# PL.net
KiCad netlist of a schematic drawn in EAGLE
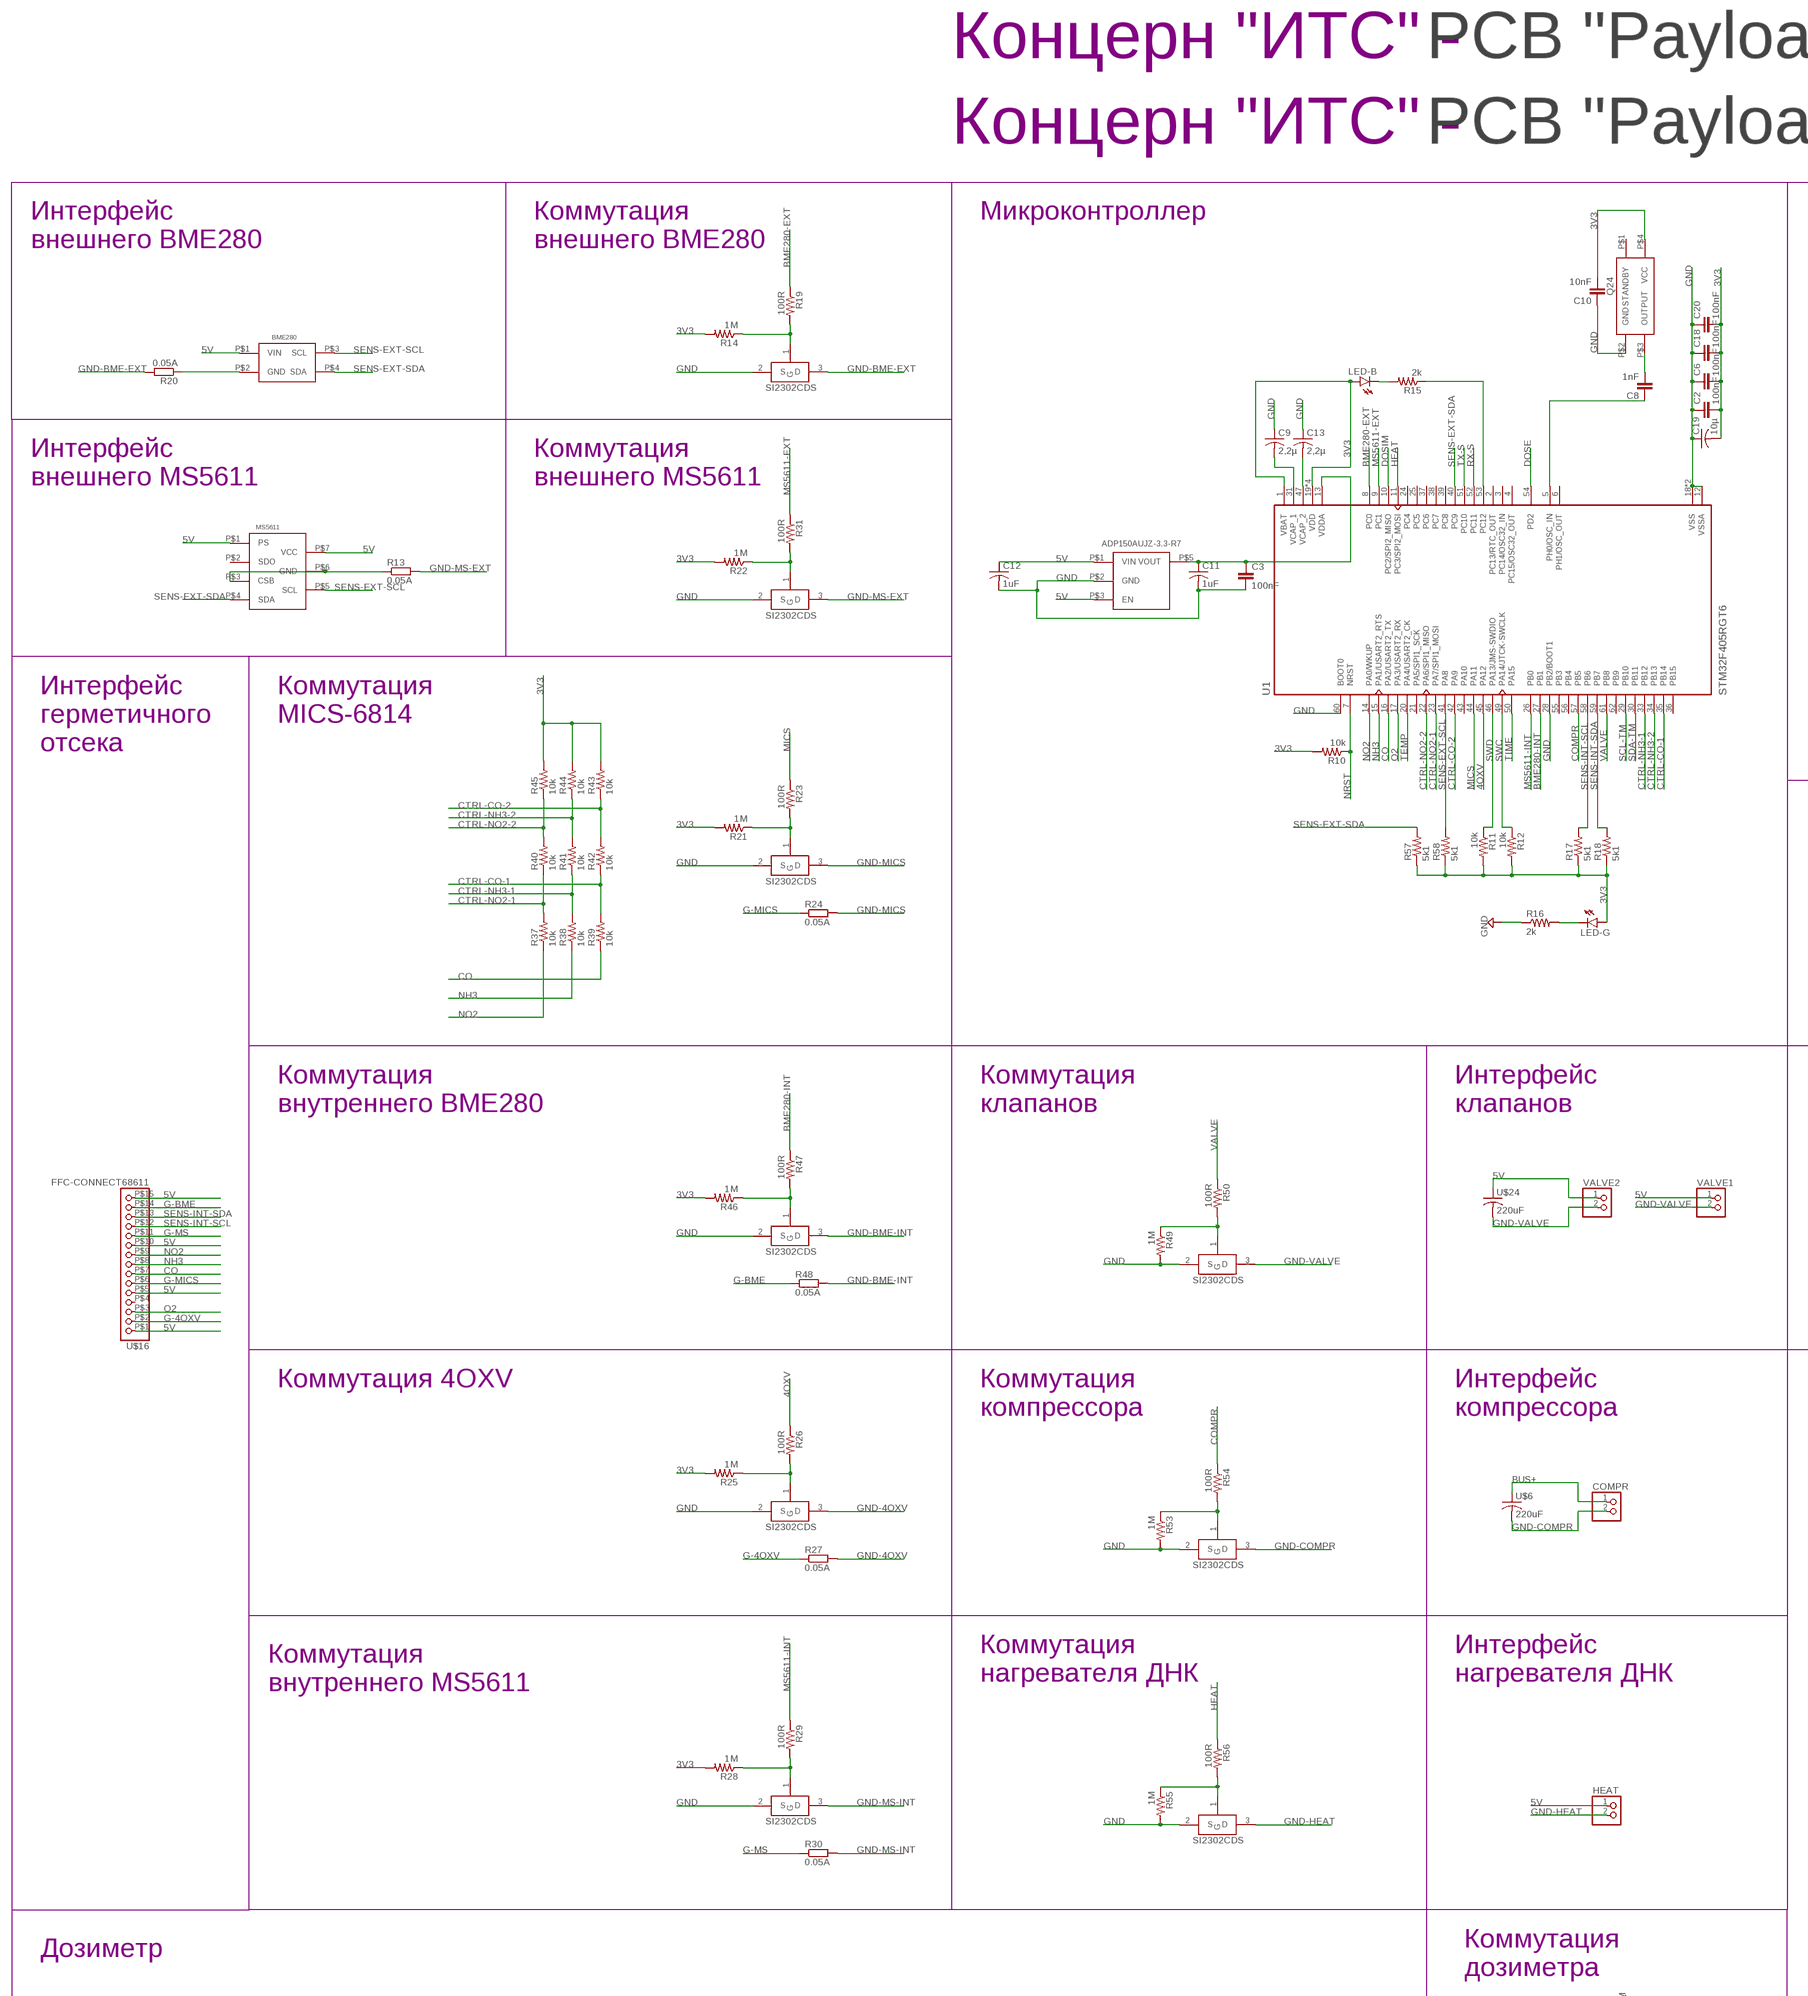
[diagram p0: schematic, sheet 1, part 1 of 3]
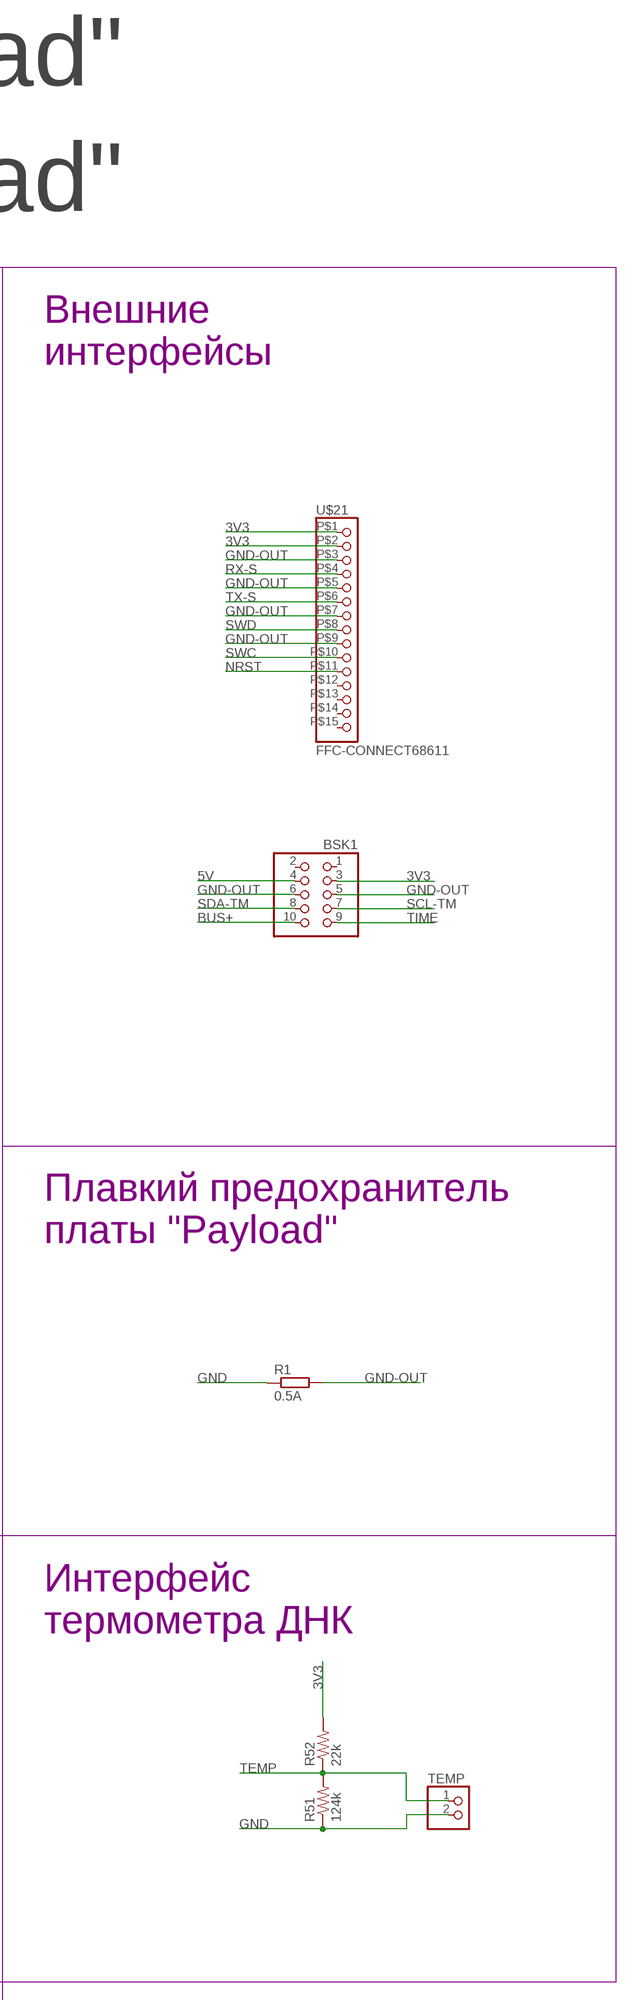
[diagram p1: schematic, sheet 1, part 2 of 3]
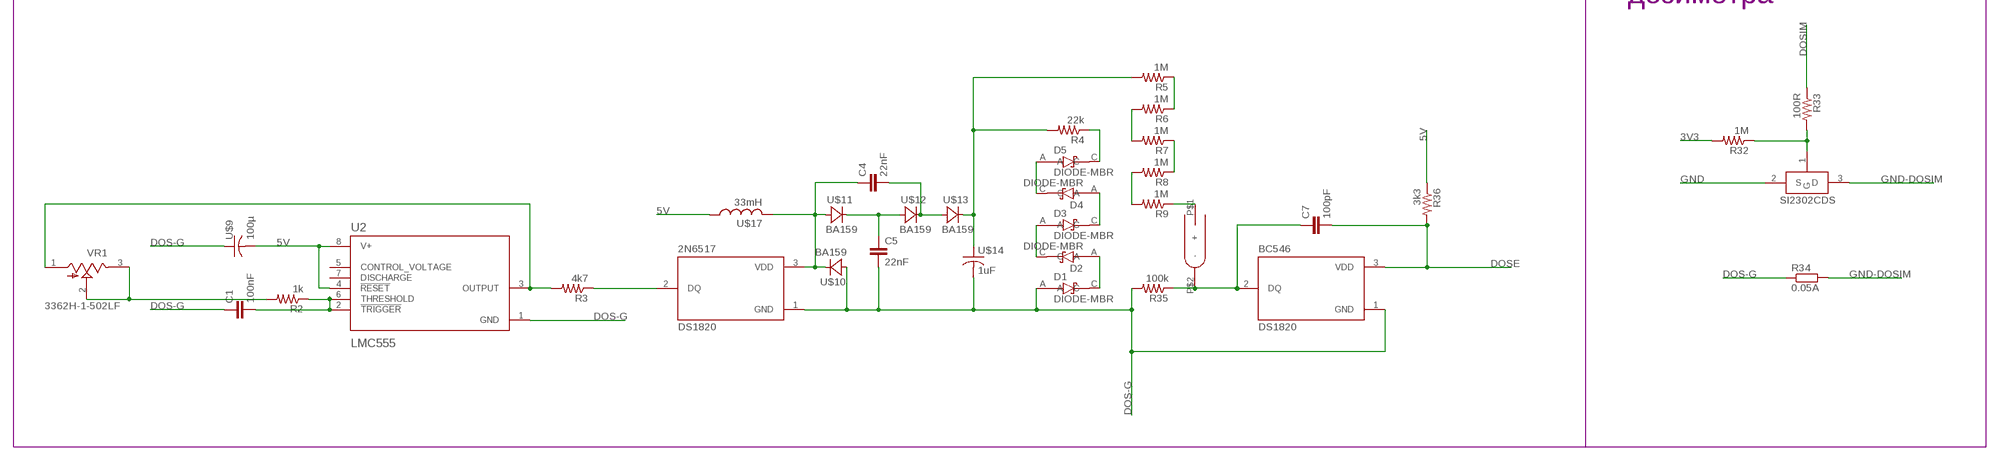
[diagram p2: schematic, sheet 1, part 3 of 3]

(export (version "E")
  (design (tool "Eeschema 10.0.6"))
  (components
    (comp (ref "2N6517")
      (value "DS1820")
      (footprint "eagle-import:TO92_TO226")
      (fields (field (name "MF") "Maxim Integrated"))
      (libsource (lib "eagle-import") (part "DS1820"))
    )
    (comp (ref "BC546")
      (value "DS1820")
      (footprint "eagle-import:TO92_TO226")
      (fields (field (name "MF") "Maxim Integrated"))
      (libsource (lib "eagle-import") (part "DS1820"))
    )
    (comp (ref "BME280")
      (value "BME280BME280-PINS-ONLY")
      (footprint "eagle-import:BME280-PINS-ONLY")
      (libsource (lib "eagle-import") (part "BME280BME280-PINS-ONLY"))
    )
    (comp (ref "BSK1")
      (value "PINHD-2X5")
      (footprint "eagle-import:2X05")
      (libsource (lib "eagle-import") (part "PINHD-2X5"))
    )
    (comp (ref "C1")
      (value "100nF")
      (footprint "eagle-import:C0603")
      (libsource (lib "eagle-import") (part "C-EUC0603"))
    )
    (comp (ref "C2")
      (value "100nF")
      (footprint "eagle-import:C0603")
      (libsource (lib "eagle-import") (part "C-EUC0603"))
    )
    (comp (ref "C3")
      (value "100nF")
      (footprint "eagle-import:C0603")
      (libsource (lib "eagle-import") (part "C-EUC0603"))
    )
    (comp (ref "C4")
      (value "22nF")
      (footprint "eagle-import:C1210")
      (libsource (lib "eagle-import") (part "C-EUC1210"))
    )
    (comp (ref "C5")
      (value "22nF")
      (footprint "eagle-import:C1210")
      (libsource (lib "eagle-import") (part "C-EUC1210"))
    )
    (comp (ref "C6")
      (value "100nF")
      (footprint "eagle-import:C0603")
      (libsource (lib "eagle-import") (part "C-EUC0603"))
    )
    (comp (ref "C7")
      (value "100pF")
      (footprint "eagle-import:C0603")
      (libsource (lib "eagle-import") (part "C-EUC0603"))
    )
    (comp (ref "C8")
      (value "1nF")
      (footprint "eagle-import:C0603")
      (libsource (lib "eagle-import") (part "C-EUC0603"))
    )
    (comp (ref "C9")
      (value "2,2µ")
      (footprint "eagle-import:C0603")
      (libsource (lib "eagle-import") (part "C-USC0603"))
    )
    (comp (ref "C10")
      (value "10nF")
      (footprint "eagle-import:C0603")
      (libsource (lib "eagle-import") (part "C-EUC0603"))
    )
    (comp (ref "C11")
      (value "1uF")
      (footprint "eagle-import:ECAP-SMD-D4")
      (libsource (lib "eagle-import") (part "ECAP1UF"))
    )
    (comp (ref "C12")
      (value "1uF")
      (footprint "eagle-import:ECAP-SMD-D4")
      (libsource (lib "eagle-import") (part "ECAP1UF"))
    )
    (comp (ref "C13")
      (value "2,2µ")
      (footprint "eagle-import:C0603")
      (libsource (lib "eagle-import") (part "C-USC0603"))
    )
    (comp (ref "C18")
      (value "100nF")
      (footprint "eagle-import:C0603")
      (libsource (lib "eagle-import") (part "C-EUC0603"))
    )
    (comp (ref "C19")
      (value "10µ")
      (footprint "eagle-import:C1206")
      (libsource (lib "eagle-import") (part "C-USC1206"))
    )
    (comp (ref "C20")
      (value "100nF")
      (footprint "eagle-import:C0603")
      (libsource (lib "eagle-import") (part "C-EUC0603"))
    )
    (comp (ref "COMPR")
      (value "PINHD-1X2")
      (footprint "eagle-import:1X02")
      (libsource (lib "eagle-import") (part "PINHD-1X2"))
    )
    (comp (ref "D1")
      (value "DIODE-MBR")
      (footprint "eagle-import:SOD123")
      (fields (field (name "MF") "ON Semiconductor") (field (name "MP") "MBR0520LT1G"))
      (libsource (lib "eagle-import") (part "DIODE-MBR"))
    )
    (comp (ref "D2")
      (value "DIODE-MBR")
      (footprint "eagle-import:SOD123")
      (fields (field (name "MF") "ON Semiconductor") (field (name "MP") "MBR0520LT1G"))
      (libsource (lib "eagle-import") (part "DIODE-MBR"))
    )
    (comp (ref "D3")
      (value "DIODE-MBR")
      (footprint "eagle-import:SOD123")
      (fields (field (name "MF") "ON Semiconductor") (field (name "MP") "MBR0520LT1G"))
      (libsource (lib "eagle-import") (part "DIODE-MBR"))
    )
    (comp (ref "D4")
      (value "DIODE-MBR")
      (footprint "eagle-import:SOD123")
      (fields (field (name "MF") "ON Semiconductor") (field (name "MP") "MBR0520LT1G"))
      (libsource (lib "eagle-import") (part "DIODE-MBR"))
    )
    (comp (ref "D5")
      (value "DIODE-MBR")
      (footprint "eagle-import:SOD123")
      (fields (field (name "MF") "ON Semiconductor") (field (name "MP") "MBR0520LT1G"))
      (libsource (lib "eagle-import") (part "DIODE-MBR"))
    )
    (comp (ref "HEAT")
      (value "PINHD-1X2")
      (footprint "eagle-import:1X02")
      (libsource (lib "eagle-import") (part "PINHD-1X2"))
    )
    (comp (ref "LED-B")
      (value "LEDCHIPLED_0603")
      (footprint "eagle-import:CHIPLED_0603")
      (libsource (lib "eagle-import") (part "LEDCHIPLED_0603"))
    )
    (comp (ref "LED-G")
      (value "LEDCHIPLED_0603")
      (footprint "eagle-import:CHIPLED_0603")
      (libsource (lib "eagle-import") (part "LEDCHIPLED_0603"))
    )
    (comp (ref "MS5611")
      (value "MS5611MS5611-PIN-ONLY")
      (footprint "eagle-import:MS5611-PINS-ONLY")
      (libsource (lib "eagle-import") (part "MS5611MS5611-PIN-ONLY"))
    )
    (comp (ref "Q24")
      (value "Q24")
      (footprint "eagle-import:Q24")
      (libsource (lib "eagle-import") (part "Q24"))
    )
    (comp (ref "R1")
      (value "0.5A")
      (footprint "eagle-import:R1210")
      (libsource (lib "eagle-import") (part "R-EU_R1210"))
    )
    (comp (ref "R2")
      (value "1k")
      (footprint "eagle-import:R0603")
      (libsource (lib "eagle-import") (part "R-US_R0603"))
    )
    (comp (ref "R3")
      (value "4k7")
      (footprint "eagle-import:R0603")
      (libsource (lib "eagle-import") (part "R-US_R0603"))
    )
    (comp (ref "R4")
      (value "22k")
      (footprint "eagle-import:R0603")
      (libsource (lib "eagle-import") (part "R-US_R0603"))
    )
    (comp (ref "R5")
      (value "1M")
      (footprint "eagle-import:R0603")
      (libsource (lib "eagle-import") (part "R-US_R0603"))
    )
    (comp (ref "R6")
      (value "1M")
      (footprint "eagle-import:R0603")
      (libsource (lib "eagle-import") (part "R-US_R0603"))
    )
    (comp (ref "R7")
      (value "1M")
      (footprint "eagle-import:R0603")
      (libsource (lib "eagle-import") (part "R-US_R0603"))
    )
    (comp (ref "R8")
      (value "1M")
      (footprint "eagle-import:R0603")
      (libsource (lib "eagle-import") (part "R-US_R0603"))
    )
    (comp (ref "R9")
      (value "1M")
      (footprint "eagle-import:R0603")
      (libsource (lib "eagle-import") (part "R-US_R0603"))
    )
    (comp (ref "R10")
      (value "10k")
      (footprint "eagle-import:R0603")
      (libsource (lib "eagle-import") (part "R-US_R0603"))
    )
    (comp (ref "R11")
      (value "10k")
      (footprint "eagle-import:R0603")
      (libsource (lib "eagle-import") (part "R-US_R0603"))
    )
    (comp (ref "R12")
      (value "10k")
      (footprint "eagle-import:R0603")
      (libsource (lib "eagle-import") (part "R-US_R0603"))
    )
    (comp (ref "R13")
      (value "0.05A")
      (footprint "eagle-import:R1210")
      (libsource (lib "eagle-import") (part "R-EU_R1210"))
    )
    (comp (ref "R14")
      (value "1M")
      (footprint "eagle-import:R0603")
      (libsource (lib "eagle-import") (part "R-US_R0603"))
    )
    (comp (ref "R15")
      (value "2k")
      (footprint "eagle-import:R0603")
      (libsource (lib "eagle-import") (part "R-US_R0603"))
    )
    (comp (ref "R16")
      (value "2k")
      (footprint "eagle-import:R0603")
      (libsource (lib "eagle-import") (part "R-US_R0603"))
    )
    (comp (ref "R17")
      (value "5k1")
      (footprint "eagle-import:R0603")
      (libsource (lib "eagle-import") (part "R-US_R0603"))
    )
    (comp (ref "R18")
      (value "5k1")
      (footprint "eagle-import:R0603")
      (libsource (lib "eagle-import") (part "R-US_R0603"))
    )
    (comp (ref "R19")
      (value "100R")
      (footprint "eagle-import:R0603")
      (libsource (lib "eagle-import") (part "R-US_R0603"))
    )
    (comp (ref "R20")
      (value "0.05A")
      (footprint "eagle-import:R1210")
      (libsource (lib "eagle-import") (part "R-EU_R1210"))
    )
    (comp (ref "R21")
      (value "1M")
      (footprint "eagle-import:R0603")
      (libsource (lib "eagle-import") (part "R-US_R0603"))
    )
    (comp (ref "R22")
      (value "1M")
      (footprint "eagle-import:R0603")
      (libsource (lib "eagle-import") (part "R-US_R0603"))
    )
    (comp (ref "R23")
      (value "100R")
      (footprint "eagle-import:R0603")
      (libsource (lib "eagle-import") (part "R-US_R0603"))
    )
    (comp (ref "R24")
      (value "0.05A")
      (footprint "eagle-import:R1210")
      (libsource (lib "eagle-import") (part "R-EU_R1210"))
    )
    (comp (ref "R25")
      (value "1M")
      (footprint "eagle-import:R0603")
      (libsource (lib "eagle-import") (part "R-US_R0603"))
    )
    (comp (ref "R26")
      (value "100R")
      (footprint "eagle-import:R0603")
      (libsource (lib "eagle-import") (part "R-US_R0603"))
    )
    (comp (ref "R27")
      (value "0.05A")
      (footprint "eagle-import:R1210")
      (libsource (lib "eagle-import") (part "R-EU_R1210"))
    )
    (comp (ref "R28")
      (value "1M")
      (footprint "eagle-import:R0603")
      (libsource (lib "eagle-import") (part "R-US_R0603"))
    )
    (comp (ref "R29")
      (value "100R")
      (footprint "eagle-import:R0603")
      (libsource (lib "eagle-import") (part "R-US_R0603"))
    )
    (comp (ref "R30")
      (value "0.05A")
      (footprint "eagle-import:R1210")
      (libsource (lib "eagle-import") (part "R-EU_R1210"))
    )
    (comp (ref "R31")
      (value "100R")
      (footprint "eagle-import:R0603")
      (libsource (lib "eagle-import") (part "R-US_R0603"))
    )
    (comp (ref "R32")
      (value "1M")
      (footprint "eagle-import:R0603")
      (libsource (lib "eagle-import") (part "R-US_R0603"))
    )
    (comp (ref "R33")
      (value "100R")
      (footprint "eagle-import:R0603")
      (libsource (lib "eagle-import") (part "R-US_R0603"))
    )
    (comp (ref "R34")
      (value "0.05A")
      (footprint "eagle-import:R1210")
      (libsource (lib "eagle-import") (part "R-EU_R1210"))
    )
    (comp (ref "R35")
      (value "100k")
      (footprint "eagle-import:R0603")
      (libsource (lib "eagle-import") (part "R-US_R0603"))
    )
    (comp (ref "R36")
      (value "3k3")
      (footprint "eagle-import:R0603")
      (libsource (lib "eagle-import") (part "R-US_R0603"))
    )
    (comp (ref "R37")
      (value "10k")
      (footprint "eagle-import:R0603")
      (libsource (lib "eagle-import") (part "resistor_348_R-US_R0603"))
    )
    (comp (ref "R38")
      (value "10k")
      (footprint "eagle-import:R0603")
      (libsource (lib "eagle-import") (part "resistor_348_R-US_R0603"))
    )
    (comp (ref "R39")
      (value "10k")
      (footprint "eagle-import:R0603")
      (libsource (lib "eagle-import") (part "resistor_348_R-US_R0603"))
    )
    (comp (ref "R40")
      (value "10k")
      (footprint "eagle-import:R0603")
      (libsource (lib "eagle-import") (part "resistor_348_R-US_R0603"))
    )
    (comp (ref "R41")
      (value "10k")
      (footprint "eagle-import:R0603")
      (libsource (lib "eagle-import") (part "resistor_348_R-US_R0603"))
    )
    (comp (ref "R42")
      (value "10k")
      (footprint "eagle-import:R0603")
      (libsource (lib "eagle-import") (part "resistor_348_R-US_R0603"))
    )
    (comp (ref "R43")
      (value "10k")
      (footprint "eagle-import:R0603")
      (libsource (lib "eagle-import") (part "resistor_348_R-US_R0603"))
    )
    (comp (ref "R44")
      (value "10k")
      (footprint "eagle-import:R0603")
      (libsource (lib "eagle-import") (part "resistor_348_R-US_R0603"))
    )
    (comp (ref "R45")
      (value "10k")
      (footprint "eagle-import:R0603")
      (libsource (lib "eagle-import") (part "resistor_348_R-US_R0603"))
    )
    (comp (ref "R46")
      (value "1M")
      (footprint "eagle-import:R0603")
      (libsource (lib "eagle-import") (part "R-US_R0603"))
    )
    (comp (ref "R47")
      (value "100R")
      (footprint "eagle-import:R0603")
      (libsource (lib "eagle-import") (part "R-US_R0603"))
    )
    (comp (ref "R48")
      (value "0.05A")
      (footprint "eagle-import:R1210")
      (libsource (lib "eagle-import") (part "R-EU_R1210"))
    )
    (comp (ref "R49")
      (value "1M")
      (footprint "eagle-import:R0603")
      (libsource (lib "eagle-import") (part "R-US_R0603"))
    )
    (comp (ref "R50")
      (value "100R")
      (footprint "eagle-import:R0603")
      (libsource (lib "eagle-import") (part "R-US_R0603"))
    )
    (comp (ref "R51")
      (value "124k")
      (footprint "eagle-import:R0603")
      (libsource (lib "eagle-import") (part "resistor_348_R-US_R0603"))
    )
    (comp (ref "R52")
      (value "22k")
      (footprint "eagle-import:R0603")
      (libsource (lib "eagle-import") (part "resistor_348_R-US_R0603"))
    )
    (comp (ref "R53")
      (value "1M")
      (footprint "eagle-import:R0603")
      (libsource (lib "eagle-import") (part "R-US_R0603"))
    )
    (comp (ref "R54")
      (value "100R")
      (footprint "eagle-import:R0603")
      (libsource (lib "eagle-import") (part "R-US_R0603"))
    )
    (comp (ref "R55")
      (value "1M")
      (footprint "eagle-import:R0603")
      (libsource (lib "eagle-import") (part "R-US_R0603"))
    )
    (comp (ref "R56")
      (value "100R")
      (footprint "eagle-import:R0603")
      (libsource (lib "eagle-import") (part "R-US_R0603"))
    )
    (comp (ref "R57")
      (value "5k1")
      (footprint "eagle-import:R0603")
      (libsource (lib "eagle-import") (part "R-US_R0603"))
    )
    (comp (ref "R58")
      (value "5k1")
      (footprint "eagle-import:R0603")
      (libsource (lib "eagle-import") (part "R-US_R0603"))
    )
    (comp (ref "SI2302-0")
      (value "SI2302CDS")
      (footprint "eagle-import:SOT23-3")
      (libsource (lib "eagle-import") (part "SI2302CDS"))
    )
    (comp (ref "SI2302-1")
      (value "SI2302CDS")
      (footprint "eagle-import:SOT23-3")
      (libsource (lib "eagle-import") (part "SI2302CDS"))
    )
    (comp (ref "SI2302-2")
      (value "SI2302CDS")
      (footprint "eagle-import:SOT23-3")
      (libsource (lib "eagle-import") (part "SI2302CDS"))
    )
    (comp (ref "SI2302-3")
      (value "SI2302CDS")
      (footprint "eagle-import:SOT23-3")
      (libsource (lib "eagle-import") (part "SI2302CDS"))
    )
    (comp (ref "SI2302-4")
      (value "SI2302CDS")
      (footprint "eagle-import:SOT23-3")
      (libsource (lib "eagle-import") (part "SI2302CDS"))
    )
    (comp (ref "SI2302-5")
      (value "SI2302CDS")
      (footprint "eagle-import:SOT23-3")
      (libsource (lib "eagle-import") (part "SI2302CDS"))
    )
    (comp (ref "SI2302-6")
      (value "SI2302CDS")
      (footprint "eagle-import:SOT23-3")
      (libsource (lib "eagle-import") (part "SI2302CDS"))
    )
    (comp (ref "SI2302-7")
      (value "SI2302CDS")
      (footprint "eagle-import:SOT23-3")
      (libsource (lib "eagle-import") (part "SI2302CDS"))
    )
    (comp (ref "SI2302-8")
      (value "SI2302CDS")
      (footprint "eagle-import:SOT23-3")
      (libsource (lib "eagle-import") (part "SI2302CDS"))
    )
    (comp (ref "SI2302-9")
      (value "SI2302CDS")
      (footprint "eagle-import:SOT23-3")
      (libsource (lib "eagle-import") (part "SI2302CDS"))
    )
    (comp (ref "STAB")
      (value "ADP150AUJZ-3.3-R7")
      (footprint "eagle-import:SOT23-5")
      (libsource (lib "eagle-import") (part "ADP150AUJZ-3.3-R7"))
    )
    (comp (ref "TEMP")
      (value "PINHD-1X2")
      (footprint "eagle-import:1X02")
      (libsource (lib "eagle-import") (part "PINHD-1X2"))
    )
    (comp (ref "U$1")
      (value "PCB \"Payload\"")
      (footprint "eagle-import:ITS-LOGO")
      (libsource (lib "eagle-import") (part "ITS-LOGOPCB-{dblquote}{dblquote}"))
    )
    (comp (ref "U$6")
      (value "220uF")
      (footprint "eagle-import:ECAP220-CMD")
      (libsource (lib "eagle-import") (part "ECAPECAP220"))
    )
    (comp (ref "U$9")
      (value "100µ")
      (footprint "eagle-import:ECAP100-CMD")
      (libsource (lib "eagle-import") (part "ECAPECAP100"))
    )
    (comp (ref "U$10")
      (value "BA159")
      (footprint "eagle-import:BA159")
      (libsource (lib "eagle-import") (part "BA159"))
    )
    (comp (ref "U$11")
      (value "BA159")
      (footprint "eagle-import:BA159")
      (libsource (lib "eagle-import") (part "BA159"))
    )
    (comp (ref "U$12")
      (value "BA159")
      (footprint "eagle-import:BA159")
      (libsource (lib "eagle-import") (part "BA159"))
    )
    (comp (ref "U$13")
      (value "BA159")
      (footprint "eagle-import:BA159")
      (libsource (lib "eagle-import") (part "BA159"))
    )
    (comp (ref "U$14")
      (value "1uF")
      (footprint "eagle-import:ECAP1MK")
      (libsource (lib "eagle-import") (part "ECAP"))
    )
    (comp (ref "U$15")
      (value "DOSIM")
      (footprint "eagle-import:DOSIM")
      (libsource (lib "eagle-import") (part "DOSIM"))
    )
    (comp (ref "U$16")
      (value "FFC-CONNECT68611")
      (footprint "eagle-import:68611")
      (libsource (lib "eagle-import") (part "FFC-CONNECT68611"))
    )
    (comp (ref "U$17")
      (value "33mH")
      (footprint "eagle-import:RCH114NP")
      (libsource (lib "eagle-import") (part "RCH114NPRCH114NP"))
    )
    (comp (ref "U$21")
      (value "FFC-CONNECT68611")
      (footprint "eagle-import:68611")
      (libsource (lib "eagle-import") (part "FFC-CONNECT68611"))
    )
    (comp (ref "U$24")
      (value "220uF")
      (footprint "eagle-import:ECAP220-CMD")
      (libsource (lib "eagle-import") (part "ECAPECAP220"))
    )
    (comp (ref "U$26")
      (value "PCB \"Payload\"")
      (footprint "eagle-import:ITS-LOGO")
      (libsource (lib "eagle-import") (part "ITS-LOGOPCB-{dblquote}{dblquote}"))
    )
    (comp (ref "U1")
      (value "STM32F405RGT6")
      (footprint "eagle-import:QFP50P1200X1200X160-64N")
      (fields (field (name "DIGI-KEY_PART_NUMBER") "497-11767-ND") (field (name "MF") "STMicroelectronics"))
      (libsource (lib "eagle-import") (part "STM32F405RGT6"))
    )
    (comp (ref "U2")
      (value "LMC555")
      (footprint "eagle-import:SOIC127P599X175-8N")
      (fields (field (name "MF") "Texas Instruments") (field (name "MP") "LMC555CMX/NOPB"))
      (libsource (lib "eagle-import") (part "LMC555CMX/NOPB"))
    )
    (comp (ref "VALVE1")
      (value "PINHD-1X2")
      (footprint "eagle-import:1X02")
      (libsource (lib "eagle-import") (part "PINHD-1X2"))
    )
    (comp (ref "VALVE2")
      (value "PINHD-1X2")
      (footprint "eagle-import:1X02")
      (libsource (lib "eagle-import") (part "PINHD-1X2"))
    )
    (comp (ref "VR1")
      (value "3362H-1-502LF")
      (footprint "eagle-import:TRIM_3362H-1-502LF")
      (fields (field (name "MF") "Bourns") (field (name "MP") "3362P-1-502LF"))
      (libsource (lib "eagle-import") (part "3362H-1-502LF"))
    )
  )
  (nets
    (net (code "1") (name "/3V3") (class "Default")
      (node (ref "BSK1") (pin "3") (pinfunction "3_3") (pintype "passive"))
      (node (ref "C10") (pin "2") (pinfunction "2_2") (pintype "passive"))
      (node (ref "C18") (pin "2") (pinfunction "2_2") (pintype "passive"))
      (node (ref "C19") (pin "2") (pinfunction "2_2") (pintype "passive"))
      (node (ref "C2") (pin "2") (pinfunction "2_2") (pintype "passive"))
      (node (ref "C20") (pin "2") (pinfunction "2_2") (pintype "passive"))
      (node (ref "C6") (pin "2") (pinfunction "2_2") (pintype "passive"))
      (node (ref "LED-B") (pin "A") (pinfunction "A_A") (pintype "passive"))
      (node (ref "LED-G") (pin "A") (pinfunction "A_A") (pintype "passive"))
      (node (ref "Q24") (pin "P$4") (pinfunction "VCC_P$4") (pintype "bidirectional"))
      (node (ref "R10") (pin "2") (pinfunction "2_2") (pintype "passive"))
      (node (ref "R11") (pin "2") (pinfunction "2_2") (pintype "passive"))
      (node (ref "R12") (pin "2") (pinfunction "2_2") (pintype "passive"))
      (node (ref "R14") (pin "2") (pinfunction "2_2") (pintype "passive"))
      (node (ref "R17") (pin "1") (pinfunction "1_1") (pintype "passive"))
      (node (ref "R18") (pin "1") (pinfunction "1_1") (pintype "passive"))
      (node (ref "R21") (pin "2") (pinfunction "2_2") (pintype "passive"))
      (node (ref "R22") (pin "2") (pinfunction "2_2") (pintype "passive"))
      (node (ref "R25") (pin "2") (pinfunction "2_2") (pintype "passive"))
      (node (ref "R28") (pin "2") (pinfunction "2_2") (pintype "passive"))
      (node (ref "R32") (pin "2") (pinfunction "2_2") (pintype "passive"))
      (node (ref "R43") (pin "2") (pinfunction "2_2") (pintype "passive"))
      (node (ref "R44") (pin "2") (pinfunction "2_2") (pintype "passive"))
      (node (ref "R45") (pin "2") (pinfunction "2_2") (pintype "passive"))
      (node (ref "R46") (pin "2") (pinfunction "2_2") (pintype "passive"))
      (node (ref "R52") (pin "2") (pinfunction "2_2") (pintype "passive"))
      (node (ref "R57") (pin "1") (pinfunction "1_1") (pintype "passive"))
      (node (ref "R58") (pin "1") (pinfunction "1_1") (pintype "passive"))
      (node (ref "U$21") (pin "P$1") (pinfunction "1_P$1") (pintype "passive"))
      (node (ref "U$21") (pin "P$2") (pinfunction "2_P$2") (pintype "passive"))
      (node (ref "U1") (pin "1") (pinfunction "VBAT_1") (pintype "power_in"))
      (node (ref "U1") (pin "19") (pinfunction "VDD_19") (pintype "power_in"))
      (node (ref "U1") (pin "32") (pinfunction "VDD_32") (pintype "power_in"))
      (node (ref "U1") (pin "48") (pinfunction "VDD_48") (pintype "power_in"))
      (node (ref "U1") (pin "64") (pinfunction "VDD_64") (pintype "power_in"))
    )
    (net (code "2") (name "/4OXV") (class "Default")
      (node (ref "R26") (pin "1") (pinfunction "1_1") (pintype "passive"))
      (node (ref "U1") (pin "45") (pinfunction "PA12_45") (pintype "bidirectional"))
    )
    (net (code "3") (name "/5V") (class "Default")
      (node (ref "BME280") (pin "P$1") (pinfunction "VIN_P$1") (pintype "bidirectional"))
      (node (ref "BSK1") (pin "4") (pinfunction "4_4") (pintype "passive"))
      (node (ref "C12") (pin "P+") (pinfunction "1_P+") (pintype "passive"))
      (node (ref "HEAT") (pin "1") (pinfunction "1_1") (pintype "passive"))
      (node (ref "MS5611") (pin "P$1") (pinfunction "PS_P$1") (pintype "bidirectional"))
      (node (ref "MS5611") (pin "P$7") (pinfunction "VCC_P$7") (pintype "bidirectional"))
      (node (ref "R36") (pin "1") (pinfunction "1_1") (pintype "passive"))
      (node (ref "STAB") (pin "P$1") (pinfunction "VIN_P$1") (pintype "bidirectional"))
      (node (ref "STAB") (pin "P$3") (pinfunction "EN_P$3") (pintype "bidirectional"))
      (node (ref "U$16") (pin "P$1") (pinfunction "1_P$1") (pintype "passive"))
      (node (ref "U$16") (pin "P$10") (pinfunction "10_P$10") (pintype "passive"))
      (node (ref "U$16") (pin "P$15") (pinfunction "15_P$15") (pintype "passive"))
      (node (ref "U$16") (pin "P$5") (pinfunction "5_P$5") (pintype "passive"))
      (node (ref "U$17") (pin "P$1") (pinfunction "1_P$1") (pintype "passive"))
      (node (ref "U$24") (pin "P$1") (pinfunction "1_P$1") (pintype "passive"))
      (node (ref "U$9") (pin "P$2") (pinfunction "2_P$2") (pintype "passive"))
      (node (ref "U2") (pin "4") (pinfunction "~{RESET}_4") (pintype "input"))
      (node (ref "U2") (pin "8") (pinfunction "V+_8") (pintype "power_in"))
      (node (ref "VALVE1") (pin "1") (pinfunction "1_1") (pintype "passive"))
      (node (ref "VALVE2") (pin "1") (pinfunction "1_1") (pintype "passive"))
    )
    (net (code "4") (name "/BME280-EXT") (class "Default")
      (node (ref "R19") (pin "1") (pinfunction "1_1") (pintype "passive"))
      (node (ref "U1") (pin "8") (pinfunction "PC0_8") (pintype "bidirectional"))
    )
    (net (code "5") (name "/BME280-INT") (class "Default")
      (node (ref "R47") (pin "1") (pinfunction "1_1") (pintype "passive"))
      (node (ref "U1") (pin "27") (pinfunction "PB1_27") (pintype "bidirectional"))
    )
    (net (code "6") (name "/BUS+") (class "Default")
      (node (ref "BSK1") (pin "10") (pinfunction "10_10") (pintype "passive"))
      (node (ref "COMPR") (pin "1") (pinfunction "1_1") (pintype "passive"))
      (node (ref "U$6") (pin "P$1") (pinfunction "1_P$1") (pintype "passive"))
    )
    (net (code "7") (name "/CO") (class "Default")
      (node (ref "R39") (pin "1") (pinfunction "1_1") (pintype "passive"))
      (node (ref "U$16") (pin "P$7") (pinfunction "7_P$7") (pintype "passive"))
      (node (ref "U1") (pin "16") (pinfunction "PA2/USART2_TX_16") (pintype "bidirectional"))
    )
    (net (code "8") (name "/COMPR") (class "Default")
      (node (ref "R54") (pin "1") (pinfunction "1_1") (pintype "passive"))
      (node (ref "U1") (pin "57") (pinfunction "PB5_57") (pintype "bidirectional"))
    )
    (net (code "9") (name "/CTRL-CO-1") (class "Default")
      (node (ref "R39") (pin "2") (pinfunction "2_2") (pintype "passive"))
      (node (ref "R42") (pin "1") (pinfunction "1_1") (pintype "passive"))
      (node (ref "U1") (pin "35") (pinfunction "PB14_35") (pintype "bidirectional"))
    )
    (net (code "10") (name "/CTRL-CO-2") (class "Default")
      (node (ref "R42") (pin "2") (pinfunction "2_2") (pintype "passive"))
      (node (ref "R43") (pin "1") (pinfunction "1_1") (pintype "passive"))
      (node (ref "U1") (pin "42") (pinfunction "PA9_42") (pintype "bidirectional"))
    )
    (net (code "11") (name "/CTRL-NH3-1") (class "Default")
      (node (ref "R38") (pin "2") (pinfunction "2_2") (pintype "passive"))
      (node (ref "R41") (pin "1") (pinfunction "1_1") (pintype "passive"))
      (node (ref "U1") (pin "33") (pinfunction "PB12_33") (pintype "bidirectional"))
    )
    (net (code "12") (name "/CTRL-NH3-2") (class "Default")
      (node (ref "R41") (pin "2") (pinfunction "2_2") (pintype "passive"))
      (node (ref "R44") (pin "1") (pinfunction "1_1") (pintype "passive"))
      (node (ref "U1") (pin "34") (pinfunction "PB13_34") (pintype "bidirectional"))
    )
    (net (code "13") (name "/CTRL-NO2-1") (class "Default")
      (node (ref "R37") (pin "2") (pinfunction "2_2") (pintype "passive"))
      (node (ref "R40") (pin "1") (pinfunction "1_1") (pintype "passive"))
      (node (ref "U1") (pin "23") (pinfunction "PA7/SPI1_MOSI_23") (pintype "bidirectional"))
    )
    (net (code "14") (name "/CTRL-NO2-2") (class "Default")
      (node (ref "R40") (pin "2") (pinfunction "2_2") (pintype "passive"))
      (node (ref "R45") (pin "1") (pinfunction "1_1") (pintype "passive"))
      (node (ref "U1") (pin "22") (pinfunction "PA6/SPI1_MISO_22") (pintype "bidirectional"))
    )
    (net (code "15") (name "/DOS-G") (class "Default")
      (node (ref "2N6517") (pin "1") (pinfunction "GND_1") (pintype "power_in"))
      (node (ref "BC546") (pin "1") (pinfunction "GND_1") (pintype "power_in"))
      (node (ref "C1") (pin "1") (pinfunction "1_1") (pintype "passive"))
      (node (ref "C5") (pin "2") (pinfunction "2_2") (pintype "passive"))
      (node (ref "D1") (pin "A") (pinfunction "A_A") (pintype "passive"))
      (node (ref "R34") (pin "1") (pinfunction "1_1") (pintype "passive"))
      (node (ref "R35") (pin "2") (pinfunction "2_2") (pintype "passive"))
      (node (ref "U$10") (pin "P$1") (pinfunction "A_P$1") (pintype "passive"))
      (node (ref "U$14") (pin "P$2") (pinfunction "2_P$2") (pintype "passive"))
      (node (ref "U$9") (pin "P$1") (pinfunction "1_P$1") (pintype "passive"))
      (node (ref "U2") (pin "1") (pinfunction "GND_1") (pintype "power_in"))
    )
    (net (code "16") (name "/DOSE") (class "Default")
      (node (ref "BC546") (pin "3") (pinfunction "VDD_3") (pintype "power_in"))
      (node (ref "C7") (pin "2") (pinfunction "2_2") (pintype "passive"))
      (node (ref "R36") (pin "2") (pinfunction "2_2") (pintype "passive"))
      (node (ref "U1") (pin "54") (pinfunction "PD2_54") (pintype "bidirectional"))
    )
    (net (code "17") (name "/DOSIM") (class "Default")
      (node (ref "R33") (pin "1") (pinfunction "1_1") (pintype "passive"))
      (node (ref "U1") (pin "10") (pinfunction "PC2/SPI2_MISO_10") (pintype "bidirectional"))
    )
    (net (code "18") (name "/G-4OXV") (class "Default")
      (node (ref "R27") (pin "1") (pinfunction "1_1") (pintype "passive"))
      (node (ref "U$16") (pin "P$2") (pinfunction "2_P$2") (pintype "passive"))
    )
    (net (code "19") (name "/G-BME") (class "Default")
      (node (ref "R48") (pin "1") (pinfunction "1_1") (pintype "passive"))
      (node (ref "U$16") (pin "P$14") (pinfunction "14_P$14") (pintype "passive"))
    )
    (net (code "20") (name "/G-MICS") (class "Default")
      (node (ref "R24") (pin "1") (pinfunction "1_1") (pintype "passive"))
      (node (ref "U$16") (pin "P$6") (pinfunction "6_P$6") (pintype "passive"))
    )
    (net (code "21") (name "/G-MS") (class "Default")
      (node (ref "R30") (pin "1") (pinfunction "1_1") (pintype "passive"))
      (node (ref "U$16") (pin "P$11") (pinfunction "11_P$11") (pintype "passive"))
    )
    (net (code "22") (name "/GND-4OXV") (class "Default")
      (node (ref "R27") (pin "2") (pinfunction "2_2") (pintype "passive"))
      (node (ref "SI2302-8") (pin "3") (pinfunction "D_3") (pintype "bidirectional"))
    )
    (net (code "23") (name "/GND-BME-EXT") (class "Default")
      (node (ref "R20") (pin "2") (pinfunction "2_2") (pintype "passive"))
      (node (ref "SI2302-2") (pin "3") (pinfunction "D_3") (pintype "bidirectional"))
    )
    (net (code "24") (name "/GND-BME-INT") (class "Default")
      (node (ref "R48") (pin "2") (pinfunction "2_2") (pintype "passive"))
      (node (ref "SI2302-5") (pin "3") (pinfunction "D_3") (pintype "bidirectional"))
    )
    (net (code "25") (name "/GND-COMPR") (class "Default")
      (node (ref "COMPR") (pin "2") (pinfunction "2_2") (pintype "passive"))
      (node (ref "SI2302-9") (pin "3") (pinfunction "D_3") (pintype "bidirectional"))
      (node (ref "U$6") (pin "P$2") (pinfunction "2_P$2") (pintype "passive"))
    )
    (net (code "26") (name "/GND-DOSIM") (class "Default")
      (node (ref "R34") (pin "2") (pinfunction "2_2") (pintype "passive"))
      (node (ref "SI2302-4") (pin "3") (pinfunction "D_3") (pintype "bidirectional"))
    )
    (net (code "27") (name "/GND-HEAT") (class "Default")
      (node (ref "HEAT") (pin "2") (pinfunction "2_2") (pintype "passive"))
      (node (ref "SI2302-3") (pin "3") (pinfunction "D_3") (pintype "bidirectional"))
    )
    (net (code "28") (name "/GND-MICS") (class "Default")
      (node (ref "R24") (pin "2") (pinfunction "2_2") (pintype "passive"))
      (node (ref "SI2302-7") (pin "3") (pinfunction "D_3") (pintype "bidirectional"))
    )
    (net (code "29") (name "/GND-MS-EXT") (class "Default")
      (node (ref "R13") (pin "2") (pinfunction "2_2") (pintype "passive"))
      (node (ref "SI2302-1") (pin "3") (pinfunction "D_3") (pintype "bidirectional"))
    )
    (net (code "30") (name "/GND-MS-INT") (class "Default")
      (node (ref "R30") (pin "2") (pinfunction "2_2") (pintype "passive"))
      (node (ref "SI2302-6") (pin "3") (pinfunction "D_3") (pintype "bidirectional"))
    )
    (net (code "31") (name "/GND-OUT") (class "Default")
      (node (ref "BSK1") (pin "5") (pinfunction "5_5") (pintype "passive"))
      (node (ref "BSK1") (pin "6") (pinfunction "6_6") (pintype "passive"))
      (node (ref "R1") (pin "2") (pinfunction "2_2") (pintype "passive"))
      (node (ref "U$21") (pin "P$3") (pinfunction "3_P$3") (pintype "passive"))
      (node (ref "U$21") (pin "P$5") (pinfunction "5_P$5") (pintype "passive"))
      (node (ref "U$21") (pin "P$7") (pinfunction "7_P$7") (pintype "passive"))
      (node (ref "U$21") (pin "P$9") (pinfunction "9_P$9") (pintype "passive"))
    )
    (net (code "32") (name "/GND-VALVE") (class "Default")
      (node (ref "SI2302-0") (pin "3") (pinfunction "D_3") (pintype "bidirectional"))
      (node (ref "U$24") (pin "P$2") (pinfunction "2_P$2") (pintype "passive"))
      (node (ref "VALVE1") (pin "2") (pinfunction "2_2") (pintype "passive"))
      (node (ref "VALVE2") (pin "2") (pinfunction "2_2") (pintype "passive"))
    )
    (net (code "33") (name "/HEAT") (class "Default")
      (node (ref "R56") (pin "1") (pinfunction "1_1") (pintype "passive"))
      (node (ref "U1") (pin "11") (pinfunction "PC3/SPI2_MOSI_11") (pintype "bidirectional"))
    )
    (net (code "34") (name "/MICS") (class "Default")
      (node (ref "R23") (pin "1") (pinfunction "1_1") (pintype "passive"))
      (node (ref "U1") (pin "44") (pinfunction "PA11_44") (pintype "bidirectional"))
    )
    (net (code "35") (name "/MS5611-EXT") (class "Default")
      (node (ref "R31") (pin "1") (pinfunction "1_1") (pintype "passive"))
      (node (ref "U1") (pin "9") (pinfunction "PC1_9") (pintype "bidirectional"))
    )
    (net (code "36") (name "/MS5611-INT") (class "Default")
      (node (ref "R29") (pin "1") (pinfunction "1_1") (pintype "passive"))
      (node (ref "U1") (pin "26") (pinfunction "PB0_26") (pintype "bidirectional"))
    )
    (net (code "37") (name "/NH3") (class "Default")
      (node (ref "R38") (pin "1") (pinfunction "1_1") (pintype "passive"))
      (node (ref "U$16") (pin "P$8") (pinfunction "8_P$8") (pintype "passive"))
      (node (ref "U1") (pin "15") (pinfunction "PA1/USART2_RTS_15") (pintype "bidirectional"))
    )
    (net (code "38") (name "/NO2") (class "Default")
      (node (ref "R37") (pin "1") (pinfunction "1_1") (pintype "passive"))
      (node (ref "U$16") (pin "P$9") (pinfunction "9_P$9") (pintype "passive"))
      (node (ref "U1") (pin "14") (pinfunction "PA0/WKUP_14") (pintype "bidirectional"))
    )
    (net (code "39") (name "/NRST") (class "Default")
      (node (ref "R10") (pin "1") (pinfunction "1_1") (pintype "passive"))
      (node (ref "U$21") (pin "P$11") (pinfunction "11_P$11") (pintype "passive"))
      (node (ref "U1") (pin "7") (pinfunction "NRST_7") (pintype "bidirectional"))
    )
    (net (code "40") (name "/O2") (class "Default")
      (node (ref "U$16") (pin "P$3") (pinfunction "3_P$3") (pintype "passive"))
      (node (ref "U1") (pin "17") (pinfunction "PA3/USART2_RX_17") (pintype "bidirectional"))
    )
    (net (code "41") (name "/RX-S") (class "Default")
      (node (ref "U$21") (pin "P$4") (pinfunction "4_P$4") (pintype "passive"))
      (node (ref "U1") (pin "52") (pinfunction "PC11_52") (pintype "bidirectional"))
    )
    (net (code "42") (name "/SCL-TM") (class "Default")
      (node (ref "BSK1") (pin "7") (pinfunction "7_7") (pintype "passive"))
      (node (ref "U1") (pin "29") (pinfunction "PB10_29") (pintype "bidirectional"))
    )
    (net (code "43") (name "/SDA-TM") (class "Default")
      (node (ref "BSK1") (pin "8") (pinfunction "8_8") (pintype "passive"))
      (node (ref "U1") (pin "30") (pinfunction "PB11_30") (pintype "bidirectional"))
    )
    (net (code "44") (name "/SENS-EXT-SCL") (class "Default")
      (node (ref "BME280") (pin "P$3") (pinfunction "SCL_P$3") (pintype "bidirectional"))
      (node (ref "MS5611") (pin "P$5") (pinfunction "SCL_P$5") (pintype "bidirectional"))
      (node (ref "R58") (pin "2") (pinfunction "2_2") (pintype "passive"))
      (node (ref "U1") (pin "41") (pinfunction "PA8_41") (pintype "bidirectional"))
    )
    (net (code "45") (name "/SENS-EXT-SDA") (class "Default")
      (node (ref "BME280") (pin "P$4") (pinfunction "SDA_P$4") (pintype "bidirectional"))
      (node (ref "MS5611") (pin "P$4") (pinfunction "SDA_P$4") (pintype "bidirectional"))
      (node (ref "R57") (pin "2") (pinfunction "2_2") (pintype "passive"))
      (node (ref "U1") (pin "40") (pinfunction "PC9_40") (pintype "bidirectional"))
    )
    (net (code "46") (name "/SENS-INT-SCL") (class "Default")
      (node (ref "R17") (pin "2") (pinfunction "2_2") (pintype "passive"))
      (node (ref "U$16") (pin "P$12") (pinfunction "12_P$12") (pintype "passive"))
      (node (ref "U1") (pin "58") (pinfunction "PB6_58") (pintype "bidirectional"))
    )
    (net (code "47") (name "/SENS-INT-SDA") (class "Default")
      (node (ref "R18") (pin "2") (pinfunction "2_2") (pintype "passive"))
      (node (ref "U$16") (pin "P$13") (pinfunction "13_P$13") (pintype "passive"))
      (node (ref "U1") (pin "59") (pinfunction "PB7_59") (pintype "bidirectional"))
    )
    (net (code "48") (name "/SWC") (class "Default")
      (node (ref "R12") (pin "1") (pinfunction "1_1") (pintype "passive"))
      (node (ref "U$21") (pin "P$10") (pinfunction "10_P$10") (pintype "passive"))
      (node (ref "U1") (pin "49") (pinfunction "PA14/JTCK-SWCLK_49") (pintype "bidirectional"))
    )
    (net (code "49") (name "/SWD") (class "Default")
      (node (ref "R11") (pin "1") (pinfunction "1_1") (pintype "passive"))
      (node (ref "U$21") (pin "P$8") (pinfunction "8_P$8") (pintype "passive"))
      (node (ref "U1") (pin "46") (pinfunction "PA13/JMS-SWDIO_46") (pintype "bidirectional"))
    )
    (net (code "50") (name "/TEMP") (class "Default")
      (node (ref "R51") (pin "2") (pinfunction "2_2") (pintype "passive"))
      (node (ref "R52") (pin "1") (pinfunction "1_1") (pintype "passive"))
      (node (ref "TEMP") (pin "1") (pinfunction "1_1") (pintype "passive"))
      (node (ref "U1") (pin "20") (pinfunction "PA4/USART2_CK_20") (pintype "bidirectional"))
    )
    (net (code "51") (name "/TIME") (class "Default")
      (node (ref "BSK1") (pin "9") (pinfunction "9_9") (pintype "passive"))
      (node (ref "U1") (pin "50") (pinfunction "PA15_50") (pintype "bidirectional"))
    )
    (net (code "52") (name "/TX-S") (class "Default")
      (node (ref "U$21") (pin "P$6") (pinfunction "6_P$6") (pintype "passive"))
      (node (ref "U1") (pin "51") (pinfunction "PC10_51") (pintype "bidirectional"))
    )
    (net (code "53") (name "/VALVE") (class "Default")
      (node (ref "R50") (pin "1") (pinfunction "1_1") (pintype "passive"))
      (node (ref "U1") (pin "61") (pinfunction "PB8_61") (pintype "bidirectional"))
    )
    (net (code "54") (name "GND") (class "Default")
      (node (ref "C10") (pin "1") (pinfunction "1_1") (pintype "passive"))
      (node (ref "C11") (pin "P-") (pinfunction "2_P-") (pintype "passive"))
      (node (ref "C12") (pin "P-") (pinfunction "2_P-") (pintype "passive"))
      (node (ref "C13") (pin "1") (pinfunction "1_1") (pintype "passive"))
      (node (ref "C18") (pin "1") (pinfunction "1_1") (pintype "passive"))
      (node (ref "C19") (pin "1") (pinfunction "1_1") (pintype "passive"))
      (node (ref "C2") (pin "1") (pinfunction "1_1") (pintype "passive"))
      (node (ref "C20") (pin "1") (pinfunction "1_1") (pintype "passive"))
      (node (ref "C3") (pin "2") (pinfunction "2_2") (pintype "passive"))
      (node (ref "C6") (pin "1") (pinfunction "1_1") (pintype "passive"))
      (node (ref "C9") (pin "1") (pinfunction "1_1") (pintype "passive"))
      (node (ref "Q24") (pin "P$2") (pinfunction "GND_P$2") (pintype "bidirectional"))
      (node (ref "R1") (pin "1") (pinfunction "1_1") (pintype "passive"))
      (node (ref "R16") (pin "1") (pinfunction "1_1") (pintype "passive"))
      (node (ref "R49") (pin "2") (pinfunction "2_2") (pintype "passive"))
      (node (ref "R51") (pin "1") (pinfunction "1_1") (pintype "passive"))
      (node (ref "R53") (pin "2") (pinfunction "2_2") (pintype "passive"))
      (node (ref "R55") (pin "2") (pinfunction "2_2") (pintype "passive"))
      (node (ref "SI2302-0") (pin "2") (pinfunction "S_2") (pintype "bidirectional"))
      (node (ref "SI2302-1") (pin "2") (pinfunction "S_2") (pintype "bidirectional"))
      (node (ref "SI2302-2") (pin "2") (pinfunction "S_2") (pintype "bidirectional"))
      (node (ref "SI2302-3") (pin "2") (pinfunction "S_2") (pintype "bidirectional"))
      (node (ref "SI2302-4") (pin "2") (pinfunction "S_2") (pintype "bidirectional"))
      (node (ref "SI2302-5") (pin "2") (pinfunction "S_2") (pintype "bidirectional"))
      (node (ref "SI2302-6") (pin "2") (pinfunction "S_2") (pintype "bidirectional"))
      (node (ref "SI2302-7") (pin "2") (pinfunction "S_2") (pintype "bidirectional"))
      (node (ref "SI2302-8") (pin "2") (pinfunction "S_2") (pintype "bidirectional"))
      (node (ref "SI2302-9") (pin "2") (pinfunction "S_2") (pintype "bidirectional"))
      (node (ref "STAB") (pin "P$2") (pinfunction "GND_P$2") (pintype "bidirectional"))
      (node (ref "TEMP") (pin "2") (pinfunction "2_2") (pintype "passive"))
      (node (ref "U1") (pin "12") (pinfunction "VSSA_12") (pintype "power_in"))
      (node (ref "U1") (pin "18") (pinfunction "VSS_18") (pintype "power_in"))
      (node (ref "U1") (pin "28") (pinfunction "PB2/BOOT1_28") (pintype "bidirectional"))
      (node (ref "U1") (pin "60") (pinfunction "BOOT0_60") (pintype "bidirectional"))
      (node (ref "U1") (pin "63") (pinfunction "VSS_63") (pintype "power_in"))
    )
    (net (code "55") (name "Net-(2N6517-DQ)") (class "Default")
      (node (ref "2N6517") (pin "2") (pinfunction "DQ_2") (pintype "bidirectional"))
      (node (ref "R3") (pin "1") (pinfunction "1_1") (pintype "passive"))
    )
    (net (code "56") (name "Net-(2N6517-VDD)") (class "Default")
      (node (ref "2N6517") (pin "3") (pinfunction "VDD_3") (pintype "power_in"))
      (node (ref "C4") (pin "1") (pinfunction "1_1") (pintype "passive"))
      (node (ref "U$10") (pin "P$2") (pinfunction "C_P$2") (pintype "passive"))
      (node (ref "U$11") (pin "P$1") (pinfunction "A_P$1") (pintype "passive"))
      (node (ref "U$17") (pin "P$2") (pinfunction "2_P$2") (pintype "passive"))
    )
    (net (code "57") (name "Net-(BC546-DQ)") (class "Default")
      (node (ref "BC546") (pin "2") (pinfunction "DQ_2") (pintype "bidirectional"))
      (node (ref "C7") (pin "1") (pinfunction "1_1") (pintype "passive"))
      (node (ref "R35") (pin "1") (pinfunction "1_1") (pintype "passive"))
      (node (ref "U$15") (pin "P$2") (pinfunction "-_P$2") (pintype "bidirectional"))
    )
    (net (code "58") (name "Net-(BME280-GND)") (class "Default")
      (node (ref "BME280") (pin "P$2") (pinfunction "GND_P$2") (pintype "bidirectional"))
      (node (ref "R20") (pin "1") (pinfunction "1_1") (pintype "passive"))
    )
    (net (code "59") (name "Net-(C11-1)") (class "Default")
      (node (ref "C11") (pin "P+") (pinfunction "1_P+") (pintype "passive"))
      (node (ref "C3") (pin "1") (pinfunction "1_1") (pintype "passive"))
      (node (ref "STAB") (pin "P$5") (pinfunction "VOUT_P$5") (pintype "bidirectional"))
      (node (ref "U1") (pin "13") (pinfunction "VDDA_13") (pintype "power_in"))
    )
    (net (code "60") (name "Net-(D1-PadC)") (class "Default")
      (node (ref "D1") (pin "C") (pinfunction "C_C") (pintype "passive"))
      (node (ref "D2") (pin "A") (pinfunction "A_A") (pintype "passive"))
    )
    (net (code "61") (name "Net-(D2-PadC)") (class "Default")
      (node (ref "D2") (pin "C") (pinfunction "C_C") (pintype "passive"))
      (node (ref "D3") (pin "A") (pinfunction "A_A") (pintype "passive"))
    )
    (net (code "62") (name "Net-(D3-PadC)") (class "Default")
      (node (ref "D3") (pin "C") (pinfunction "C_C") (pintype "passive"))
      (node (ref "D4") (pin "A") (pinfunction "A_A") (pintype "passive"))
    )
    (net (code "63") (name "Net-(D4-PadC)") (class "Default")
      (node (ref "D4") (pin "C") (pinfunction "C_C") (pintype "passive"))
      (node (ref "D5") (pin "A") (pinfunction "A_A") (pintype "passive"))
    )
    (net (code "64") (name "Net-(D5-PadC)") (class "Default")
      (node (ref "D5") (pin "C") (pinfunction "C_C") (pintype "passive"))
      (node (ref "R4") (pin "1") (pinfunction "1_1") (pintype "passive"))
    )
    (net (code "65") (name "Net-(LED-B-PadC)") (class "Default")
      (node (ref "LED-B") (pin "C") (pinfunction "C_C") (pintype "passive"))
      (node (ref "R15") (pin "2") (pinfunction "2_2") (pintype "passive"))
    )
    (net (code "66") (name "Net-(LED-G-PadC)") (class "Default")
      (node (ref "LED-G") (pin "C") (pinfunction "C_C") (pintype "passive"))
      (node (ref "R16") (pin "2") (pinfunction "2_2") (pintype "passive"))
    )
    (net (code "67") (name "Net-(MS5611-CSB)") (class "Default")
      (node (ref "MS5611") (pin "P$3") (pinfunction "CSB_P$3") (pintype "bidirectional"))
      (node (ref "MS5611") (pin "P$6") (pinfunction "GND_P$6") (pintype "bidirectional"))
      (node (ref "R13") (pin "1") (pinfunction "1_1") (pintype "passive"))
    )
    (net (code "68") (name "Net-(Q24-OUTPUT)") (class "Default")
      (node (ref "C8") (pin "2") (pinfunction "2_2") (pintype "passive"))
      (node (ref "Q24") (pin "P$3") (pinfunction "OUTPUT_P$3") (pintype "bidirectional"))
    )
    (net (code "69") (name "Net-(R5-Pad1)") (class "Default")
      (node (ref "R5") (pin "1") (pinfunction "1_1") (pintype "passive"))
      (node (ref "R6") (pin "1") (pinfunction "1_1") (pintype "passive"))
    )
    (net (code "70") (name "Net-(R6-Pad2)") (class "Default")
      (node (ref "R6") (pin "2") (pinfunction "2_2") (pintype "passive"))
      (node (ref "R7") (pin "2") (pinfunction "2_2") (pintype "passive"))
    )
    (net (code "71") (name "Net-(R7-Pad1)") (class "Default")
      (node (ref "R7") (pin "1") (pinfunction "1_1") (pintype "passive"))
      (node (ref "R8") (pin "1") (pinfunction "1_1") (pintype "passive"))
    )
    (net (code "72") (name "Net-(R8-Pad2)") (class "Default")
      (node (ref "R8") (pin "2") (pinfunction "2_2") (pintype "passive"))
      (node (ref "R9") (pin "2") (pinfunction "2_2") (pintype "passive"))
    )
    (net (code "73") (name "Net-(SI2302-0-G)") (class "Default")
      (node (ref "R49") (pin "1") (pinfunction "1_1") (pintype "passive"))
      (node (ref "R50") (pin "2") (pinfunction "2_2") (pintype "passive"))
      (node (ref "SI2302-0") (pin "1") (pinfunction "G_1") (pintype "bidirectional"))
    )
    (net (code "74") (name "Net-(SI2302-1-G)") (class "Default")
      (node (ref "R22") (pin "1") (pinfunction "1_1") (pintype "passive"))
      (node (ref "R31") (pin "2") (pinfunction "2_2") (pintype "passive"))
      (node (ref "SI2302-1") (pin "1") (pinfunction "G_1") (pintype "bidirectional"))
    )
    (net (code "75") (name "Net-(SI2302-2-G)") (class "Default")
      (node (ref "R14") (pin "1") (pinfunction "1_1") (pintype "passive"))
      (node (ref "R19") (pin "2") (pinfunction "2_2") (pintype "passive"))
      (node (ref "SI2302-2") (pin "1") (pinfunction "G_1") (pintype "bidirectional"))
    )
    (net (code "76") (name "Net-(SI2302-3-G)") (class "Default")
      (node (ref "R55") (pin "1") (pinfunction "1_1") (pintype "passive"))
      (node (ref "R56") (pin "2") (pinfunction "2_2") (pintype "passive"))
      (node (ref "SI2302-3") (pin "1") (pinfunction "G_1") (pintype "bidirectional"))
    )
    (net (code "77") (name "Net-(SI2302-4-G)") (class "Default")
      (node (ref "R32") (pin "1") (pinfunction "1_1") (pintype "passive"))
      (node (ref "R33") (pin "2") (pinfunction "2_2") (pintype "passive"))
      (node (ref "SI2302-4") (pin "1") (pinfunction "G_1") (pintype "bidirectional"))
    )
    (net (code "78") (name "Net-(SI2302-5-G)") (class "Default")
      (node (ref "R46") (pin "1") (pinfunction "1_1") (pintype "passive"))
      (node (ref "R47") (pin "2") (pinfunction "2_2") (pintype "passive"))
      (node (ref "SI2302-5") (pin "1") (pinfunction "G_1") (pintype "bidirectional"))
    )
    (net (code "79") (name "Net-(SI2302-6-G)") (class "Default")
      (node (ref "R28") (pin "1") (pinfunction "1_1") (pintype "passive"))
      (node (ref "R29") (pin "2") (pinfunction "2_2") (pintype "passive"))
      (node (ref "SI2302-6") (pin "1") (pinfunction "G_1") (pintype "bidirectional"))
    )
    (net (code "80") (name "Net-(SI2302-7-G)") (class "Default")
      (node (ref "R21") (pin "1") (pinfunction "1_1") (pintype "passive"))
      (node (ref "R23") (pin "2") (pinfunction "2_2") (pintype "passive"))
      (node (ref "SI2302-7") (pin "1") (pinfunction "G_1") (pintype "bidirectional"))
    )
    (net (code "81") (name "Net-(SI2302-8-G)") (class "Default")
      (node (ref "R25") (pin "1") (pinfunction "1_1") (pintype "passive"))
      (node (ref "R26") (pin "2") (pinfunction "2_2") (pintype "passive"))
      (node (ref "SI2302-8") (pin "1") (pinfunction "G_1") (pintype "bidirectional"))
    )
    (net (code "82") (name "Net-(SI2302-9-G)") (class "Default")
      (node (ref "R53") (pin "1") (pinfunction "1_1") (pintype "passive"))
      (node (ref "R54") (pin "2") (pinfunction "2_2") (pintype "passive"))
      (node (ref "SI2302-9") (pin "1") (pinfunction "G_1") (pintype "bidirectional"))
    )
    (net (code "83") (name "Net-(U$11-C)") (class "Default")
      (node (ref "C5") (pin "1") (pinfunction "1_1") (pintype "passive"))
      (node (ref "U$11") (pin "P$2") (pinfunction "C_P$2") (pintype "passive"))
      (node (ref "U$12") (pin "P$1") (pinfunction "A_P$1") (pintype "passive"))
    )
    (net (code "84") (name "Net-(U$12-C)") (class "Default")
      (node (ref "C4") (pin "2") (pinfunction "2_2") (pintype "passive"))
      (node (ref "U$12") (pin "P$2") (pinfunction "C_P$2") (pintype "passive"))
      (node (ref "U$13") (pin "P$1") (pinfunction "A_P$1") (pintype "passive"))
    )
    (net (code "85") (name "Net-(U$13-C)") (class "Default")
      (node (ref "R4") (pin "2") (pinfunction "2_2") (pintype "passive"))
      (node (ref "R5") (pin "2") (pinfunction "2_2") (pintype "passive"))
      (node (ref "U$13") (pin "P$2") (pinfunction "C_P$2") (pintype "passive"))
      (node (ref "U$14") (pin "P$1") (pinfunction "1_P$1") (pintype "passive"))
    )
    (net (code "86") (name "Net-(U$15-+)") (class "Default")
      (node (ref "R9") (pin "1") (pinfunction "1_1") (pintype "passive"))
      (node (ref "U$15") (pin "P$1") (pinfunction "+_P$1") (pintype "bidirectional"))
    )
    (net (code "87") (name "Net-(U1-PC12)") (class "Default")
      (node (ref "R15") (pin "1") (pinfunction "1_1") (pintype "passive"))
      (node (ref "U1") (pin "53") (pinfunction "PC12_53") (pintype "bidirectional"))
    )
    (net (code "88") (name "Net-(U1-PH0{slash}OSC_IN)") (class "Default")
      (node (ref "C8") (pin "1") (pinfunction "1_1") (pintype "passive"))
      (node (ref "U1") (pin "5") (pinfunction "PH0/OSC_IN_5") (pintype "bidirectional"))
    )
    (net (code "89") (name "Net-(U1-VCAP_1)") (class "Default")
      (node (ref "C9") (pin "2") (pinfunction "2_2") (pintype "passive"))
      (node (ref "U1") (pin "31") (pinfunction "VCAP_1_31") (pintype "power_in"))
    )
    (net (code "90") (name "Net-(U1-VCAP_2)") (class "Default")
      (node (ref "C13") (pin "2") (pinfunction "2_2") (pintype "passive"))
      (node (ref "U1") (pin "47") (pinfunction "VCAP_2_47") (pintype "power_in"))
    )
    (net (code "91") (name "Net-(U2-OUTPUT)") (class "Default")
      (node (ref "R3") (pin "2") (pinfunction "2_2") (pintype "passive"))
      (node (ref "U2") (pin "3") (pinfunction "OUTPUT_3") (pintype "output"))
      (node (ref "VR1") (pin "1") (pinfunction "CCW_1") (pintype "passive"))
    )
    (net (code "92") (name "Net-(U2-THRESHOLD)") (class "Default")
      (node (ref "C1") (pin "2") (pinfunction "2_2") (pintype "passive"))
      (node (ref "R2") (pin "1") (pinfunction "1_1") (pintype "passive"))
      (node (ref "U2") (pin "2") (pinfunction "~{TRIGGER}_2") (pintype "input"))
      (node (ref "U2") (pin "6") (pinfunction "THRESHOLD_6") (pintype "input"))
    )
    (net (code "93") (name "Net-(VR1-CW)") (class "Default")
      (node (ref "R2") (pin "2") (pinfunction "2_2") (pintype "passive"))
      (node (ref "VR1") (pin "2") (pinfunction "WIPER_2") (pintype "passive"))
      (node (ref "VR1") (pin "3") (pinfunction "CW_3") (pintype "passive"))
    )
    (net (code "94") (name "unconnected-(BSK1-Pad1)") (class "Default")
      (node (ref "BSK1") (pin "1") (pinfunction "1_1") (pintype "passive"))
    )
    (net (code "95") (name "unconnected-(BSK1-Pad2)") (class "Default")
      (node (ref "BSK1") (pin "2") (pinfunction "2_2") (pintype "passive"))
    )
    (net (code "96") (name "unconnected-(MS5611-SDO-PadP$2)") (class "Default")
      (node (ref "MS5611") (pin "P$2") (pinfunction "SDO_P$2") (pintype "bidirectional"))
    )
    (net (code "97") (name "unconnected-(Q24-STANDBY-PadP$1)") (class "Default")
      (node (ref "Q24") (pin "P$1") (pinfunction "STANDBY_P$1") (pintype "bidirectional"))
    )
    (net (code "98") (name "unconnected-(U$16-4-PadP$4)") (class "Default")
      (node (ref "U$16") (pin "P$4") (pinfunction "4_P$4") (pintype "passive"))
    )
    (net (code "99") (name "unconnected-(U$21-12-PadP$12)") (class "Default")
      (node (ref "U$21") (pin "P$12") (pinfunction "12_P$12") (pintype "passive"))
    )
    (net (code "100") (name "unconnected-(U$21-13-PadP$13)") (class "Default")
      (node (ref "U$21") (pin "P$13") (pinfunction "13_P$13") (pintype "passive"))
    )
    (net (code "101") (name "unconnected-(U$21-14-PadP$14)") (class "Default")
      (node (ref "U$21") (pin "P$14") (pinfunction "14_P$14") (pintype "passive"))
    )
    (net (code "102") (name "unconnected-(U$21-15-PadP$15)") (class "Default")
      (node (ref "U$21") (pin "P$15") (pinfunction "15_P$15") (pintype "passive"))
    )
    (net (code "103") (name "unconnected-(U1-PA5{slash}SPI1_SCK-Pad21)") (class "Default")
      (node (ref "U1") (pin "21") (pinfunction "PA5/SPI1_SCK_21") (pintype "bidirectional"))
    )
    (net (code "104") (name "unconnected-(U1-PA10-Pad43)") (class "Default")
      (node (ref "U1") (pin "43") (pinfunction "PA10_43") (pintype "bidirectional"))
    )
    (net (code "105") (name "unconnected-(U1-PB3-Pad55)") (class "Default")
      (node (ref "U1") (pin "55") (pinfunction "PB3_55") (pintype "bidirectional"))
    )
    (net (code "106") (name "unconnected-(U1-PB4-Pad56)") (class "Default")
      (node (ref "U1") (pin "56") (pinfunction "PB4_56") (pintype "bidirectional"))
    )
    (net (code "107") (name "unconnected-(U1-PB9-Pad62)") (class "Default")
      (node (ref "U1") (pin "62") (pinfunction "PB9_62") (pintype "bidirectional"))
    )
    (net (code "108") (name "unconnected-(U1-PB15-Pad36)") (class "Default")
      (node (ref "U1") (pin "36") (pinfunction "PB15_36") (pintype "bidirectional"))
    )
    (net (code "109") (name "unconnected-(U1-PC4-Pad24)") (class "Default")
      (node (ref "U1") (pin "24") (pinfunction "PC4_24") (pintype "bidirectional"))
    )
    (net (code "110") (name "unconnected-(U1-PC5-Pad25)") (class "Default")
      (node (ref "U1") (pin "25") (pinfunction "PC5_25") (pintype "bidirectional"))
    )
    (net (code "111") (name "unconnected-(U1-PC6-Pad37)") (class "Default")
      (node (ref "U1") (pin "37") (pinfunction "PC6_37") (pintype "bidirectional"))
    )
    (net (code "112") (name "unconnected-(U1-PC7-Pad38)") (class "Default")
      (node (ref "U1") (pin "38") (pinfunction "PC7_38") (pintype "bidirectional"))
    )
    (net (code "113") (name "unconnected-(U1-PC8-Pad39)") (class "Default")
      (node (ref "U1") (pin "39") (pinfunction "PC8_39") (pintype "bidirectional"))
    )
    (net (code "114") (name "unconnected-(U1-PC13{slash}RTC_OUT-Pad2)") (class "Default")
      (node (ref "U1") (pin "2") (pinfunction "PC13/RTC_OUT_2") (pintype "bidirectional"))
    )
    (net (code "115") (name "unconnected-(U1-PC14{slash}OSC32_IN-Pad3)") (class "Default")
      (node (ref "U1") (pin "3") (pinfunction "PC14/OSC32_IN_3") (pintype "bidirectional"))
    )
    (net (code "116") (name "unconnected-(U1-PC15{slash}OSC32_OUT-Pad4)") (class "Default")
      (node (ref "U1") (pin "4") (pinfunction "PC15/OSC32_OUT_4") (pintype "bidirectional"))
    )
    (net (code "117") (name "unconnected-(U1-PH1{slash}OSC_OUT-Pad6)") (class "Default")
      (node (ref "U1") (pin "6") (pinfunction "PH1/OSC_OUT_6") (pintype "bidirectional"))
    )
    (net (code "118") (name "unconnected-(U2-CONTROL_VOLTAGE-Pad5)") (class "Default")
      (node (ref "U2") (pin "5") (pinfunction "CONTROL_VOLTAGE_5") (pintype "input"))
    )
    (net (code "119") (name "unconnected-(U2-DISCHARGE-Pad7)") (class "Default")
      (node (ref "U2") (pin "7") (pinfunction "DISCHARGE_7") (pintype "input"))
    )
  )
)
